# Pi_Observer.net
KiCad netlist of a schematic drawn in EAGLE
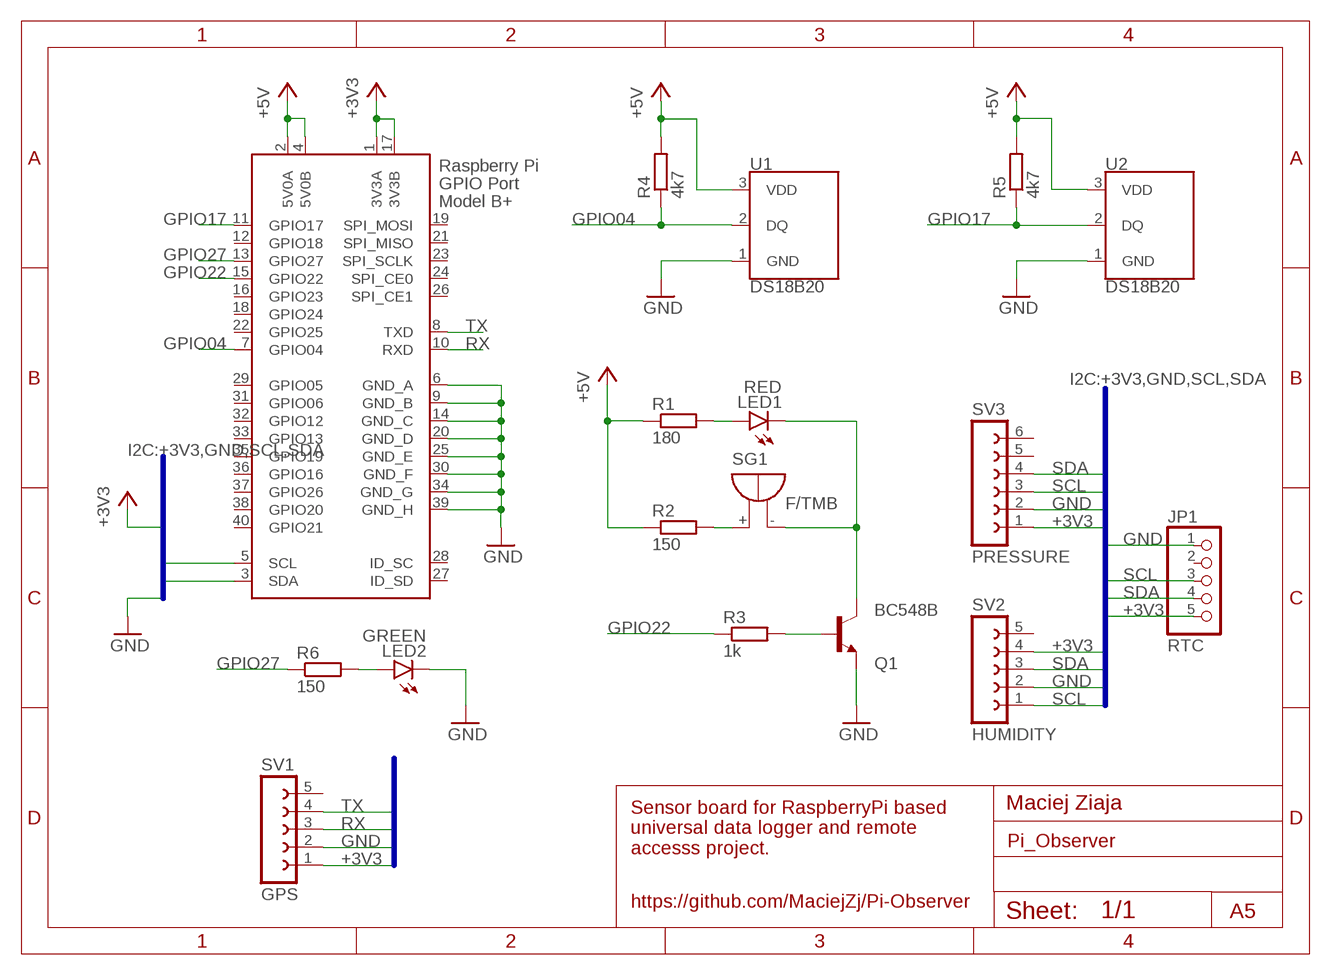
[diagram p0: schematic, sheet 1]

(export (version "E")
  (design (tool "Eeschema 10.0.6"))
  (components
    (comp (ref "JP1")
      (value "RTC")
      (footprint "eagle-import:1X05")
      (libsource (lib "eagle-import") (part "PINHD-1X5"))
    )
    (comp (ref "LED1")
      (value "RED")
      (footprint "eagle-import:LED5MM")
      (libsource (lib "eagle-import") (part "LED5MM"))
    )
    (comp (ref "LED2")
      (value "GREEN")
      (footprint "eagle-import:LED5MM")
      (libsource (lib "eagle-import") (part "LED5MM"))
    )
    (comp (ref "Q1")
      (value "BC548B")
      (footprint "eagle-import:TO92-EBC")
      (libsource (lib "eagle-import") (part "BC548B"))
    )
    (comp (ref "R1")
      (value "180")
      (footprint "eagle-import:M1206")
      (libsource (lib "eagle-import") (part "R-EU_M1206"))
    )
    (comp (ref "R2")
      (value "150")
      (footprint "eagle-import:M1206")
      (libsource (lib "eagle-import") (part "R-EU_M1206"))
    )
    (comp (ref "R3")
      (value "1k")
      (footprint "eagle-import:M1206")
      (libsource (lib "eagle-import") (part "R-EU_M1206"))
    )
    (comp (ref "R4")
      (value "4k7")
      (footprint "eagle-import:M1206")
      (libsource (lib "eagle-import") (part "R-EU_M1206"))
    )
    (comp (ref "R5")
      (value "4k7")
      (footprint "eagle-import:M1206")
      (libsource (lib "eagle-import") (part "R-EU_M1206"))
    )
    (comp (ref "R6")
      (value "150")
      (footprint "eagle-import:M1206")
      (libsource (lib "eagle-import") (part "R-EU_M1206"))
    )
    (comp (ref "SG1")
      (value "F/TMB")
      (footprint "eagle-import:F_TMB")
      (libsource (lib "eagle-import") (part "F/TMB"))
    )
    (comp (ref "SV1")
      (value "GPS")
      (footprint "eagle-import:FE05-1")
      (libsource (lib "eagle-import") (part "FE05-1"))
    )
    (comp (ref "SV2")
      (value "HUMIDITY")
      (footprint "eagle-import:FE05-1")
      (libsource (lib "eagle-import") (part "FE05-1"))
    )
    (comp (ref "SV3")
      (value "PRESSURE")
      (footprint "eagle-import:FE06")
      (libsource (lib "eagle-import") (part "FE06-1"))
    )
    (comp (ref "U1")
      (value "DS18B20")
      (footprint "eagle-import:TO-92-AMMO")
      (libsource (lib "eagle-import") (part "DS18B20"))
    )
    (comp (ref "U2")
      (value "DS18B20")
      (footprint "eagle-import:TO-92-AMMO")
      (libsource (lib "eagle-import") (part "DS18B20"))
    )
    (comp (ref "X1")
      (value "RASPI_GPIO_B+#_PIN")
      (footprint "eagle-import:RASPI_GPIO_B+_PIN")
      (libsource (lib "eagle-import") (part "RASPI_GPIO_B+#_PIN"))
    )
  )
  (nets
    (net (code "2") (name "+3V3") (class "Default")
      (node (ref "JP1") (pin "5") (pinfunction "5_5") (pintype "passive"))
      (node (ref "SV1") (pin "1") (pinfunction "1_1") (pintype "passive"))
      (node (ref "SV2") (pin "4") (pinfunction "4_4") (pintype "passive"))
      (node (ref "SV3") (pin "1") (pinfunction "1_1") (pintype "passive"))
      (node (ref "X1") (pin "1") (pinfunction "3V3A_1") (pintype "power_in"))
      (node (ref "X1") (pin "17") (pinfunction "3V3B_17") (pintype "power_in"))
    )
    (net (code "3") (name "+5V") (class "Default")
      (node (ref "R1") (pin "1") (pinfunction "1_1") (pintype "passive"))
      (node (ref "R2") (pin "1") (pinfunction "1_1") (pintype "passive"))
      (node (ref "R4") (pin "2") (pinfunction "2_2") (pintype "passive"))
      (node (ref "R5") (pin "2") (pinfunction "2_2") (pintype "passive"))
      (node (ref "U1") (pin "3") (pinfunction "VDD_3") (pintype "power_in"))
      (node (ref "U2") (pin "3") (pinfunction "VDD_3") (pintype "power_in"))
      (node (ref "X1") (pin "2") (pinfunction "5V0A_2") (pintype "power_in"))
      (node (ref "X1") (pin "4") (pinfunction "5V0B_4") (pintype "power_in"))
    )
    (net (code "4") (name "/GPIO04") (class "Default")
      (node (ref "R4") (pin "1") (pinfunction "1_1") (pintype "passive"))
      (node (ref "U1") (pin "2") (pinfunction "DQ_2") (pintype "bidirectional"))
      (node (ref "X1") (pin "7") (pinfunction "GPIO04_7") (pintype "bidirectional"))
    )
    (net (code "5") (name "/GPIO17") (class "Default")
      (node (ref "R5") (pin "1") (pinfunction "1_1") (pintype "passive"))
      (node (ref "U2") (pin "2") (pinfunction "DQ_2") (pintype "bidirectional"))
      (node (ref "X1") (pin "11") (pinfunction "GPIO17_11") (pintype "bidirectional"))
    )
    (net (code "6") (name "/GPIO22") (class "Default")
      (node (ref "R3") (pin "1") (pinfunction "1_1") (pintype "passive"))
      (node (ref "X1") (pin "15") (pinfunction "GPIO22_15") (pintype "bidirectional"))
    )
    (net (code "7") (name "/GPIO27") (class "Default")
      (node (ref "R6") (pin "1") (pinfunction "1_1") (pintype "passive"))
      (node (ref "X1") (pin "13") (pinfunction "GPIO27_13") (pintype "bidirectional"))
    )
    (net (code "8") (name "/RX") (class "Default")
      (node (ref "SV1") (pin "3") (pinfunction "3_3") (pintype "passive"))
      (node (ref "X1") (pin "10") (pinfunction "RXD_10") (pintype "bidirectional"))
    )
    (net (code "9") (name "/SCL") (class "Default")
      (node (ref "JP1") (pin "3") (pinfunction "3_3") (pintype "passive"))
      (node (ref "SV2") (pin "1") (pinfunction "1_1") (pintype "passive"))
      (node (ref "SV3") (pin "3") (pinfunction "3_3") (pintype "passive"))
      (node (ref "X1") (pin "5") (pinfunction "SCL_5") (pintype "bidirectional"))
    )
    (net (code "10") (name "/SDA") (class "Default")
      (node (ref "JP1") (pin "4") (pinfunction "4_4") (pintype "passive"))
      (node (ref "SV2") (pin "3") (pinfunction "3_3") (pintype "passive"))
      (node (ref "SV3") (pin "4") (pinfunction "4_4") (pintype "passive"))
      (node (ref "X1") (pin "3") (pinfunction "SDA_3") (pintype "bidirectional"))
    )
    (net (code "11") (name "/TX") (class "Default")
      (node (ref "SV1") (pin "4") (pinfunction "4_4") (pintype "passive"))
      (node (ref "X1") (pin "8") (pinfunction "TXD_8") (pintype "bidirectional"))
    )
    (net (code "13") (name "GND") (class "Default")
      (node (ref "JP1") (pin "1") (pinfunction "1_1") (pintype "passive"))
      (node (ref "LED2") (pin "K") (pinfunction "C_K") (pintype "passive"))
      (node (ref "Q1") (pin "E") (pinfunction "E_E") (pintype "passive"))
      (node (ref "SV1") (pin "2") (pinfunction "2_2") (pintype "passive"))
      (node (ref "SV2") (pin "2") (pinfunction "2_2") (pintype "passive"))
      (node (ref "SV3") (pin "2") (pinfunction "2_2") (pintype "passive"))
      (node (ref "U1") (pin "1") (pinfunction "GND_1") (pintype "power_in"))
      (node (ref "U2") (pin "1") (pinfunction "GND_1") (pintype "power_in"))
      (node (ref "X1") (pin "14") (pinfunction "GND_C_14") (pintype "power_in"))
      (node (ref "X1") (pin "20") (pinfunction "GND_D_20") (pintype "power_in"))
      (node (ref "X1") (pin "25") (pinfunction "GND_E_25") (pintype "power_in"))
      (node (ref "X1") (pin "30") (pinfunction "GND_F_30") (pintype "power_in"))
      (node (ref "X1") (pin "34") (pinfunction "GND_G_34") (pintype "power_in"))
      (node (ref "X1") (pin "39") (pinfunction "GND_H_39") (pintype "power_in"))
      (node (ref "X1") (pin "6") (pinfunction "GND_A_6") (pintype "power_in"))
      (node (ref "X1") (pin "9") (pinfunction "GND_B_9") (pintype "power_in"))
    )
    (net (code "14") (name "Net-(LED1-C)") (class "Default")
      (node (ref "LED1") (pin "K") (pinfunction "C_K") (pintype "passive"))
      (node (ref "Q1") (pin "C") (pinfunction "C_C") (pintype "passive"))
      (node (ref "SG1") (pin "-") (pinfunction "-_-") (pintype "passive"))
    )
    (net (code "15") (name "Net-(LED1-PadA)") (class "Default")
      (node (ref "LED1") (pin "A") (pinfunction "A_A") (pintype "passive"))
      (node (ref "R1") (pin "2") (pinfunction "2_2") (pintype "passive"))
    )
    (net (code "16") (name "Net-(LED2-PadA)") (class "Default")
      (node (ref "LED2") (pin "A") (pinfunction "A_A") (pintype "passive"))
      (node (ref "R6") (pin "2") (pinfunction "2_2") (pintype "passive"))
    )
    (net (code "17") (name "Net-(Q1-PadB)") (class "Default")
      (node (ref "Q1") (pin "B") (pinfunction "B_B") (pintype "passive"))
      (node (ref "R3") (pin "2") (pinfunction "2_2") (pintype "passive"))
    )
    (net (code "18") (name "Net-(R2-Pad2)") (class "Default")
      (node (ref "R2") (pin "2") (pinfunction "2_2") (pintype "passive"))
      (node (ref "SG1") (pin "+") (pinfunction "+_+") (pintype "passive"))
    )
    (net (code "19") (name "unconnected-(JP1-Pad2)") (class "Default")
      (node (ref "JP1") (pin "2") (pinfunction "2_2") (pintype "passive"))
    )
    (net (code "20") (name "unconnected-(SV1-Pad5)") (class "Default")
      (node (ref "SV1") (pin "5") (pinfunction "5_5") (pintype "passive"))
    )
    (net (code "21") (name "unconnected-(SV2-Pad5)") (class "Default")
      (node (ref "SV2") (pin "5") (pinfunction "5_5") (pintype "passive"))
    )
    (net (code "22") (name "unconnected-(SV3-Pad5)") (class "Default")
      (node (ref "SV3") (pin "5") (pinfunction "5_5") (pintype "passive"))
    )
    (net (code "23") (name "unconnected-(SV3-Pad6)") (class "Default")
      (node (ref "SV3") (pin "6") (pinfunction "6_6") (pintype "passive"))
    )
    (net (code "24") (name "unconnected-(X1-GPIO05-Pad29)") (class "Default")
      (node (ref "X1") (pin "29") (pinfunction "GPIO05_29") (pintype "no_connect"))
    )
    (net (code "25") (name "unconnected-(X1-GPIO06-Pad31)") (class "Default")
      (node (ref "X1") (pin "31") (pinfunction "GPIO06_31") (pintype "no_connect"))
    )
    (net (code "26") (name "unconnected-(X1-GPIO12-Pad32)") (class "Default")
      (node (ref "X1") (pin "32") (pinfunction "GPIO12_32") (pintype "no_connect"))
    )
    (net (code "27") (name "unconnected-(X1-GPIO13-Pad33)") (class "Default")
      (node (ref "X1") (pin "33") (pinfunction "GPIO13_33") (pintype "no_connect"))
    )
    (net (code "28") (name "unconnected-(X1-GPIO16-Pad36)") (class "Default")
      (node (ref "X1") (pin "36") (pinfunction "GPIO16_36") (pintype "no_connect"))
    )
    (net (code "29") (name "unconnected-(X1-GPIO18-Pad12)") (class "Default")
      (node (ref "X1") (pin "12") (pinfunction "GPIO18_12") (pintype "bidirectional"))
    )
    (net (code "30") (name "unconnected-(X1-GPIO19-Pad35)") (class "Default")
      (node (ref "X1") (pin "35") (pinfunction "GPIO19_35") (pintype "no_connect"))
    )
    (net (code "31") (name "unconnected-(X1-GPIO20-Pad38)") (class "Default")
      (node (ref "X1") (pin "38") (pinfunction "GPIO20_38") (pintype "no_connect"))
    )
    (net (code "32") (name "unconnected-(X1-GPIO21-Pad40)") (class "Default")
      (node (ref "X1") (pin "40") (pinfunction "GPIO21_40") (pintype "no_connect"))
    )
    (net (code "33") (name "unconnected-(X1-GPIO23-Pad16)") (class "Default")
      (node (ref "X1") (pin "16") (pinfunction "GPIO23_16") (pintype "bidirectional"))
    )
    (net (code "34") (name "unconnected-(X1-GPIO24-Pad18)") (class "Default")
      (node (ref "X1") (pin "18") (pinfunction "GPIO24_18") (pintype "bidirectional"))
    )
    (net (code "35") (name "unconnected-(X1-GPIO25-Pad22)") (class "Default")
      (node (ref "X1") (pin "22") (pinfunction "GPIO25_22") (pintype "bidirectional"))
    )
    (net (code "36") (name "unconnected-(X1-GPIO26-Pad37)") (class "Default")
      (node (ref "X1") (pin "37") (pinfunction "GPIO26_37") (pintype "no_connect"))
    )
    (net (code "37") (name "unconnected-(X1-ID_SC-Pad28)") (class "Default")
      (node (ref "X1") (pin "28") (pinfunction "ID_SC_28") (pintype "no_connect"))
    )
    (net (code "38") (name "unconnected-(X1-ID_SD-Pad27)") (class "Default")
      (node (ref "X1") (pin "27") (pinfunction "ID_SD_27") (pintype "no_connect"))
    )
    (net (code "39") (name "unconnected-(X1-SPI_CE0-Pad24)") (class "Default")
      (node (ref "X1") (pin "24") (pinfunction "SPI_CE0_24") (pintype "bidirectional"))
    )
    (net (code "40") (name "unconnected-(X1-SPI_CE1-Pad26)") (class "Default")
      (node (ref "X1") (pin "26") (pinfunction "SPI_CE1_26") (pintype "bidirectional"))
    )
    (net (code "41") (name "unconnected-(X1-SPI_MISO-Pad21)") (class "Default")
      (node (ref "X1") (pin "21") (pinfunction "SPI_MISO_21") (pintype "bidirectional"))
    )
    (net (code "42") (name "unconnected-(X1-SPI_MOSI-Pad19)") (class "Default")
      (node (ref "X1") (pin "19") (pinfunction "SPI_MOSI_19") (pintype "bidirectional"))
    )
    (net (code "43") (name "unconnected-(X1-SPI_SCLK-Pad23)") (class "Default")
      (node (ref "X1") (pin "23") (pinfunction "SPI_SCLK_23") (pintype "bidirectional"))
    )
  )
)
